# dental-uint-pedal_v1_0.net
KiCad netlist of a schematic drawn in Altium Designer
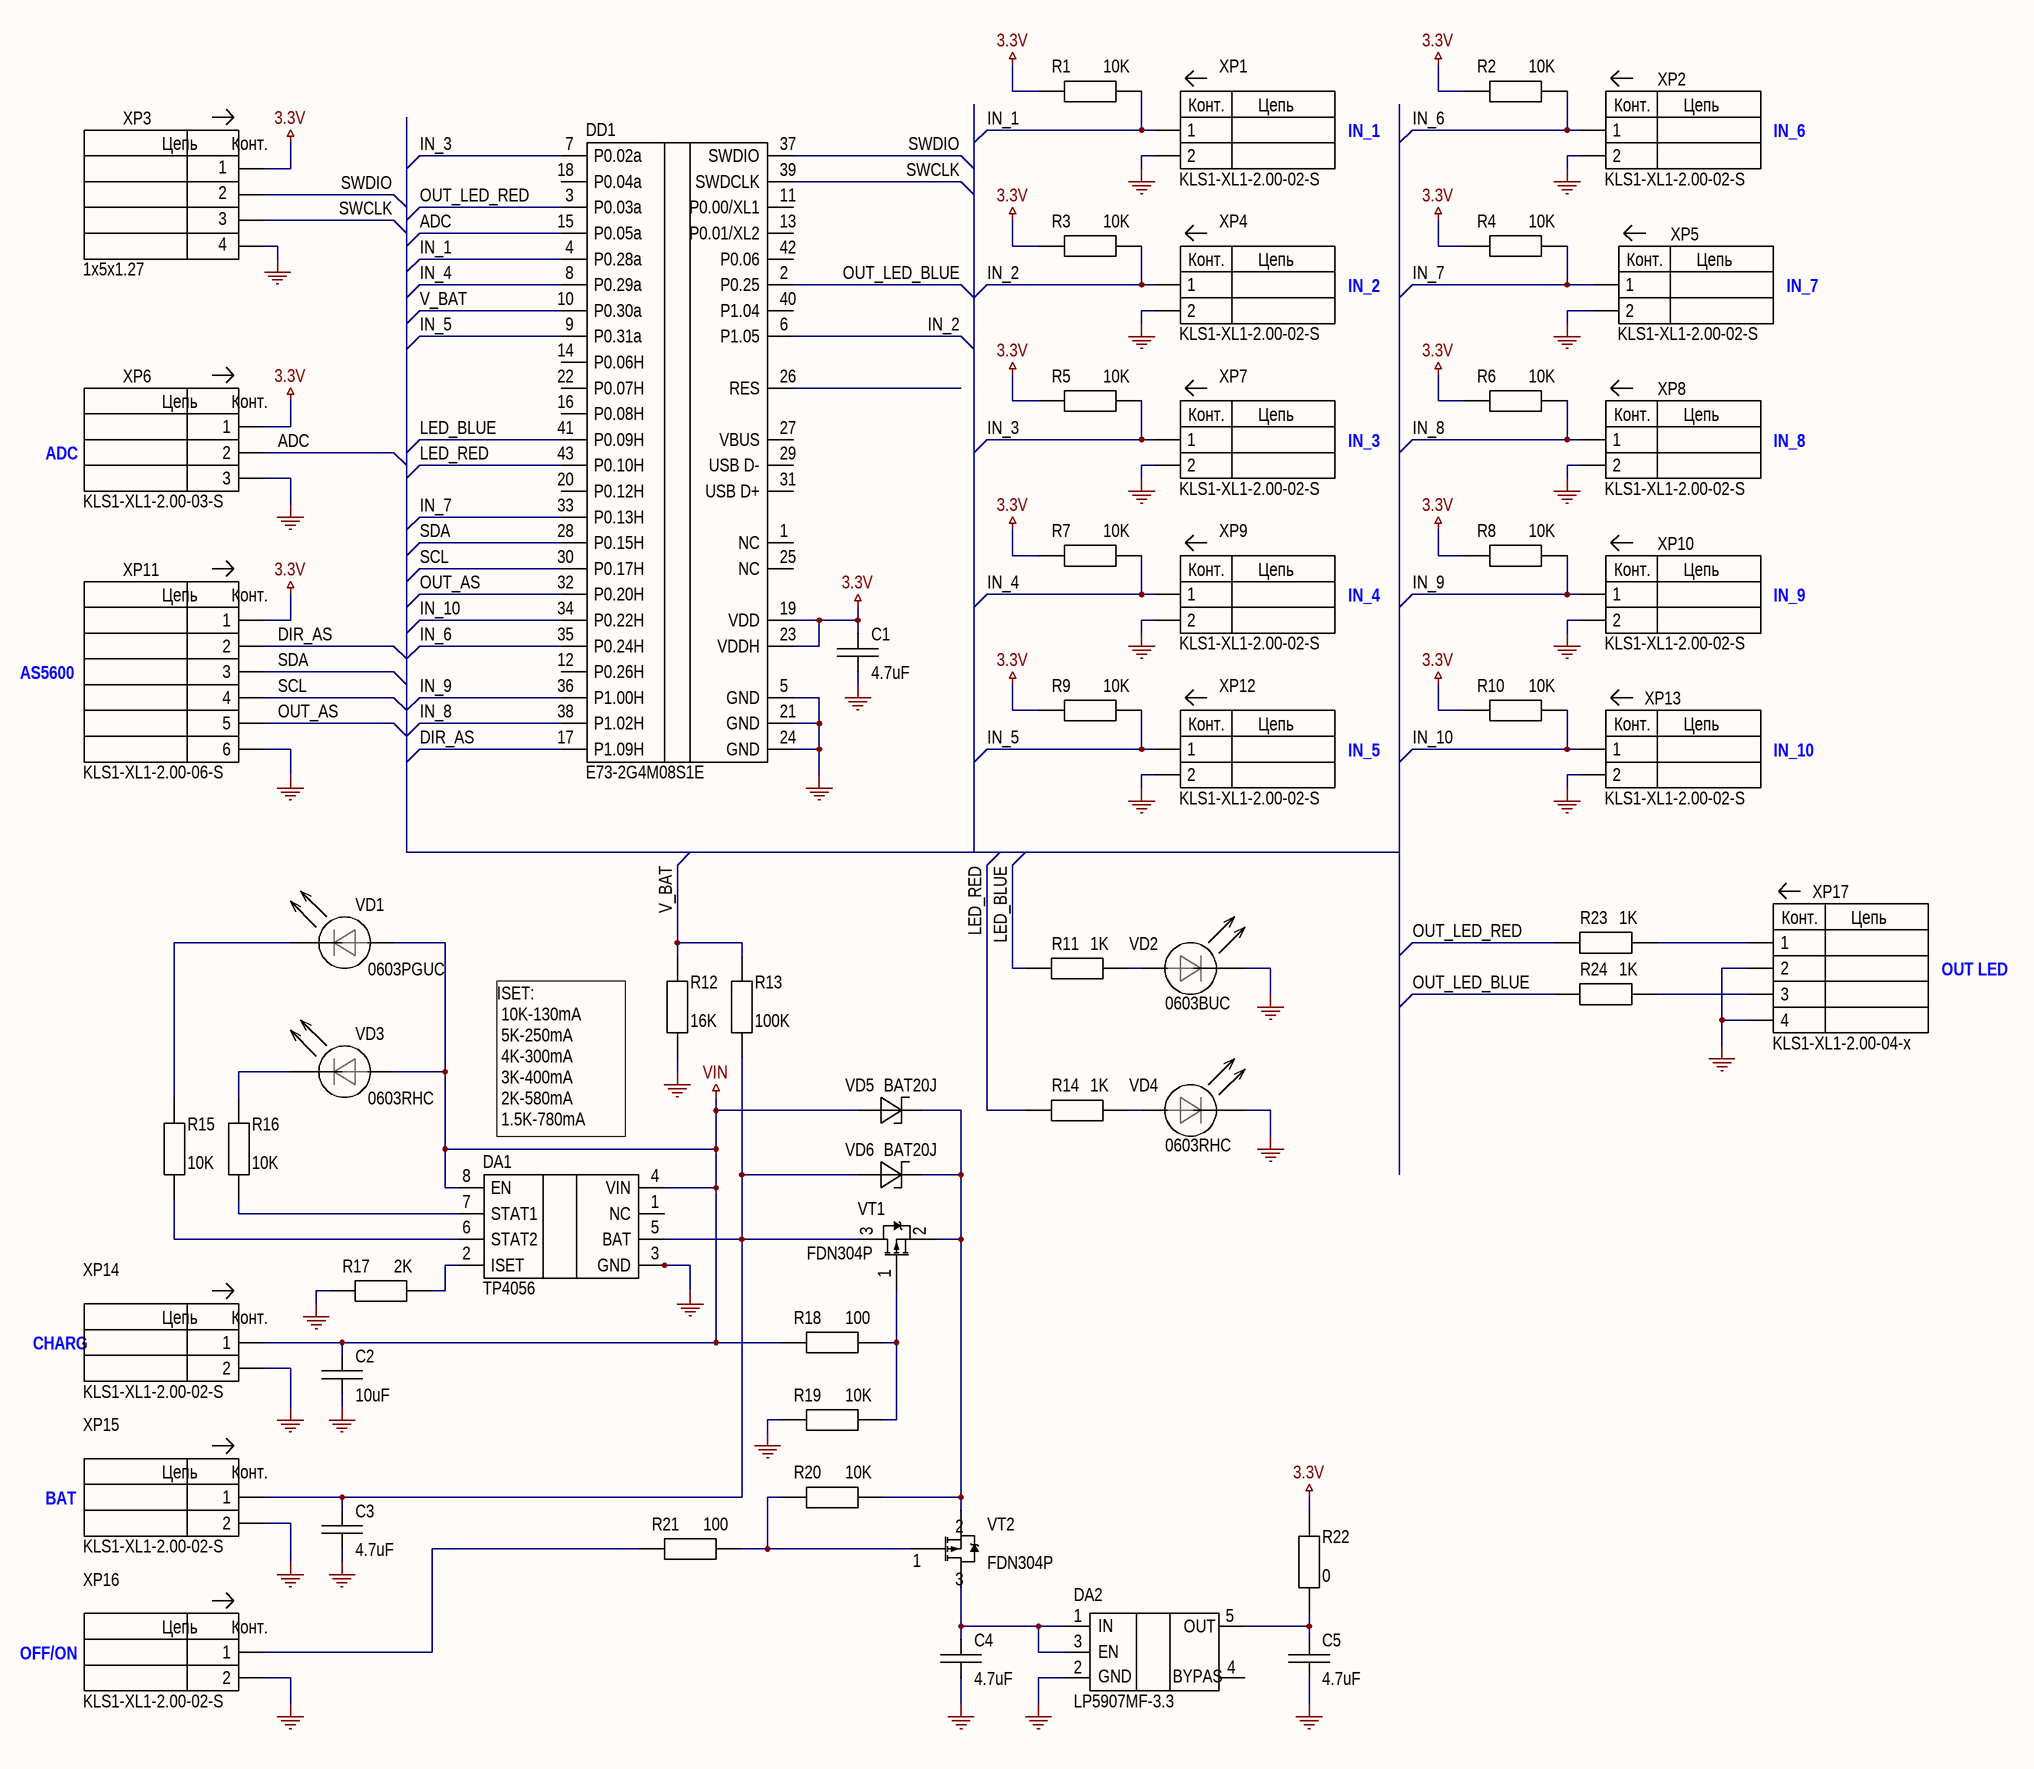
[diagram p0: dental-uint-pedal v1_0.SchDoc]

(export (version "E")
  (design (tool "Eeschema 10.0.6"))
  (components
    (comp (ref "C1")
      (value "4.7uF")
      (footprint "CC_0603")
      (description "Cap Ceramic, 0603, 4.7u, 10%, 25V, X5R (Sumsung)")
      (fields (field (name "Comment") "CL10A475KA8NQNC"))
      (libsource (lib "my_discrete_new") (part "C"))
    )
    (comp (ref "C2")
      (value "10uF")
      (footprint "CC_0603")
      (description "Cap Ceramic, 0603, 10u, 10%, 16V, X5R (Sumsung)")
      (fields (field (name "Comment") "CL10A106KP8NNNC"))
      (libsource (lib "my_discrete_new") (part "C"))
    )
    (comp (ref "C3")
      (value "4.7uF")
      (footprint "CC_0603")
      (description "Cap Ceramic, 0603, 4.7u, 10%, 25V, X5R (Sumsung)")
      (fields (field (name "Comment") "CL10A475KA8NQNC"))
      (libsource (lib "my_discrete_new") (part "C"))
    )
    (comp (ref "C4")
      (value "4.7uF")
      (footprint "CC_0603")
      (description "Cap Ceramic, 0603, 4.7u, 10%, 25V, X5R (Sumsung)")
      (fields (field (name "Comment") "CL10A475KA8NQNC"))
      (libsource (lib "my_discrete_new") (part "C"))
    )
    (comp (ref "C5")
      (value "4.7uF")
      (footprint "CC_0603")
      (description "Cap Ceramic, 0603, 4.7u, 10%, 25V, X5R (Sumsung)")
      (fields (field (name "Comment") "CL10A475KA8NQNC"))
      (libsource (lib "my_discrete_new") (part "C"))
    )
    (comp (ref "DA1")
      (value "TP4056")
      (footprint "SOIC-8N")
      (description "Battery Management")
      (libsource (lib "my_microschems_new") (part "TP4056"))
    )
    (comp (ref "DA2")
      (value "LP5907MF-3.3")
      (footprint "SOT-23-5")
      (description "LDO, SOT-23-5, 3.3v, 0.25А, @TI")
      (libsource (lib "my_microschems_new") (part "LP5907MF-3.3"))
    )
    (comp (ref "DD1")
      (value "E73-2G4M08S1E")
      (footprint "E73-2G4M08S1C")
      (description "nRF52833")
      (libsource (lib "my_microschems_new") (part "E73-2G4M08S1E"))
    )
    (comp (ref "R1")
      (value "10K")
      (footprint "RC_0603")
      (description "Res, 0603, 10K, 1%, 0.25W (ф. Yageo)")
      (fields (field (name "POWER") "0.25W") (field (name "Comment") "AC0603FR-0710KL"))
      (libsource (lib "my_discrete_new") (part "R"))
    )
    (comp (ref "R2")
      (value "10K")
      (footprint "RC_0603")
      (description "Res, 0603, 10K, 1%, 0.25W (ф. Yageo)")
      (fields (field (name "POWER") "0.25W") (field (name "Comment") "AC0603FR-0710KL"))
      (libsource (lib "my_discrete_new") (part "R"))
    )
    (comp (ref "R3")
      (value "10K")
      (footprint "RC_0603")
      (description "Res, 0603, 10K, 1%, 0.25W (ф. Yageo)")
      (fields (field (name "POWER") "0.25W") (field (name "Comment") "AC0603FR-0710KL"))
      (libsource (lib "my_discrete_new") (part "R"))
    )
    (comp (ref "R4")
      (value "10K")
      (footprint "RC_0603")
      (description "Res, 0603, 10K, 1%, 0.25W (ф. Yageo)")
      (fields (field (name "POWER") "0.25W") (field (name "Comment") "AC0603FR-0710KL"))
      (libsource (lib "my_discrete_new") (part "R"))
    )
    (comp (ref "R5")
      (value "10K")
      (footprint "RC_0603")
      (description "Res, 0603, 10K, 1%, 0.25W (ф. Yageo)")
      (fields (field (name "POWER") "0.25W") (field (name "Comment") "AC0603FR-0710KL"))
      (libsource (lib "my_discrete_new") (part "R"))
    )
    (comp (ref "R6")
      (value "10K")
      (footprint "RC_0603")
      (description "Res, 0603, 10K, 1%, 0.25W (ф. Yageo)")
      (fields (field (name "POWER") "0.25W") (field (name "Comment") "AC0603FR-0710KL"))
      (libsource (lib "my_discrete_new") (part "R"))
    )
    (comp (ref "R7")
      (value "10K")
      (footprint "RC_0603")
      (description "Res, 0603, 10K, 1%, 0.25W (ф. Yageo)")
      (fields (field (name "POWER") "0.25W") (field (name "Comment") "AC0603FR-0710KL"))
      (libsource (lib "my_discrete_new") (part "R"))
    )
    (comp (ref "R8")
      (value "10K")
      (footprint "RC_0603")
      (description "Res, 0603, 10K, 1%, 0.25W (ф. Yageo)")
      (fields (field (name "POWER") "0.25W") (field (name "Comment") "AC0603FR-0710KL"))
      (libsource (lib "my_discrete_new") (part "R"))
    )
    (comp (ref "R9")
      (value "10K")
      (footprint "RC_0603")
      (description "Res, 0603, 10K, 1%, 0.25W (ф. Yageo)")
      (fields (field (name "POWER") "0.25W") (field (name "Comment") "AC0603FR-0710KL"))
      (libsource (lib "my_discrete_new") (part "R"))
    )
    (comp (ref "R10")
      (value "10K")
      (footprint "RC_0603")
      (description "Res, 0603, 10K, 1%, 0.25W (ф. Yageo)")
      (fields (field (name "POWER") "0.25W") (field (name "Comment") "AC0603FR-0710KL"))
      (libsource (lib "my_discrete_new") (part "R"))
    )
    (comp (ref "R11")
      (value "1K")
      (footprint "RC_0603")
      (description "Res, 0603, 1K 1%, 0.25W (ф. Yageo)")
      (fields (field (name "POWER") "0.25W") (field (name "Comment") "AC0603FR-071KL"))
      (libsource (lib "my_discrete_new") (part "R"))
    )
    (comp (ref "R12")
      (value "16K")
      (footprint "RC_0603")
      (description "Res, 0603, 16K, 1%, 0.25W (ф. Yageo)")
      (fields (field (name "POWER") "0.25W") (field (name "Comment") "AC0603JR-0716KL"))
      (libsource (lib "my_discrete_new") (part "R"))
    )
    (comp (ref "R13")
      (value "100K")
      (footprint "RC_0603")
      (description "Res, 0603, 100K, 1%, 0.25W (ф. Yageo)")
      (fields (field (name "POWER") "0.25W") (field (name "Comment") "AC0603FR-07100KL"))
      (libsource (lib "my_discrete_new") (part "R"))
    )
    (comp (ref "R14")
      (value "1K")
      (footprint "RC_0603")
      (description "Res, 0603, 1K 1%, 0.25W (ф. Yageo)")
      (fields (field (name "POWER") "0.25W") (field (name "Comment") "AC0603FR-071KL"))
      (libsource (lib "my_discrete_new") (part "R"))
    )
    (comp (ref "R15")
      (value "10K")
      (footprint "RC_0603")
      (description "Res, 0603, 10K, 1%, 0.25W (ф. Yageo)")
      (fields (field (name "POWER") "0.25W") (field (name "Comment") "AC0603FR-0710KL"))
      (libsource (lib "my_discrete_new") (part "R"))
    )
    (comp (ref "R16")
      (value "10K")
      (footprint "RC_0603")
      (description "Res, 0603, 10K, 1%, 0.25W (ф. Yageo)")
      (fields (field (name "POWER") "0.25W") (field (name "Comment") "AC0603FR-0710KL"))
      (libsource (lib "my_discrete_new") (part "R"))
    )
    (comp (ref "R17")
      (value "2K")
      (footprint "RC_0603")
      (description "Res, 0603, 2K, 1%, 0.25W (ф. Yageo)")
      (fields (field (name "POWER") "0.25W") (field (name "Comment") "AC0603FR-072KL"))
      (libsource (lib "my_discrete_new") (part "R"))
    )
    (comp (ref "R18")
      (value "100")
      (footprint "RC_0603")
      (description "Res, 0603, 100, 1%, 0.25W (ф. Yageo)")
      (fields (field (name "POWER") "0.25W") (field (name "Comment") "RC0603FR-07100RL"))
      (libsource (lib "my_discrete_new") (part "R"))
    )
    (comp (ref "R19")
      (value "10K")
      (footprint "RC_0603")
      (description "Res, 0603, 10K, 1%, 0.25W (ф. Yageo)")
      (fields (field (name "POWER") "0.25W") (field (name "Comment") "AC0603FR-0710KL"))
      (libsource (lib "my_discrete_new") (part "R"))
    )
    (comp (ref "R20")
      (value "10K")
      (footprint "RC_0603")
      (description "Res, 0603, 10K, 1%, 0.25W (ф. Yageo)")
      (fields (field (name "POWER") "0.25W") (field (name "Comment") "AC0603FR-0710KL"))
      (libsource (lib "my_discrete_new") (part "R"))
    )
    (comp (ref "R21")
      (value "100")
      (footprint "RC_0603")
      (description "Res, 0603, 100, 1%, 0.25W (ф. Yageo)")
      (fields (field (name "POWER") "0.25W") (field (name "Comment") "RC0603FR-07100RL"))
      (libsource (lib "my_discrete_new") (part "R"))
    )
    (comp (ref "R22")
      (value "0")
      (footprint "RC_0603")
      (description "Res, 0603, 0, 1%, 0.25W (ф. Yageo)")
      (fields (field (name "POWER") "0.25W") (field (name "Comment") "AC0603FR-070RL"))
      (libsource (lib "my_discrete_new") (part "R"))
    )
    (comp (ref "R23")
      (value "1K")
      (footprint "RC_0603")
      (description "Res, 0603, 1K 1%, 0.25W (ф. Yageo)")
      (fields (field (name "POWER") "0.25W") (field (name "Comment") "AC0603FR-071KL"))
      (libsource (lib "my_discrete_new") (part "R"))
    )
    (comp (ref "R24")
      (value "1K")
      (footprint "RC_0603")
      (description "Res, 0603, 1K 1%, 0.25W (ф. Yageo)")
      (fields (field (name "POWER") "0.25W") (field (name "Comment") "AC0603FR-071KL"))
      (libsource (lib "my_discrete_new") (part "R"))
    )
    (comp (ref "VD1")
      (value "0603PGUC")
      (footprint "LED_0603")
      (description "Led, 0603, GREEN, 20mA, 125, 140MCD, CPMELEC")
      (libsource (lib "my_discrete_new") (part "LED"))
    )
    (comp (ref "VD2")
      (value "0603BUC")
      (footprint "LED_0603")
      (description "Led, 0603, BLUE, 20mA, 125, 140MCD, CPMELEC")
      (libsource (lib "my_discrete_new") (part "LED"))
    )
    (comp (ref "VD3")
      (value "0603RHC")
      (footprint "LED_0603")
      (description "Led, 0603, RED, 20mA, 125, 140MCD, CPMELEC")
      (libsource (lib "my_discrete_new") (part "LED"))
    )
    (comp (ref "VD4")
      (value "0603RHC")
      (footprint "LED_0603")
      (description "Led, 0603, RED, 20mA, 125, 140MCD, CPMELEC")
      (libsource (lib "my_discrete_new") (part "LED"))
    )
    (comp (ref "VD5")
      (value "BAT20J")
      (footprint "SOD-323")
      (libsource (lib "my_discrete_new") (part "D_schottky"))
    )
    (comp (ref "VD6")
      (value "BAT20J")
      (footprint "SOD-323")
      (libsource (lib "my_discrete_new") (part "D_schottky"))
    )
    (comp (ref "VT1")
      (value "FDN304P")
      (footprint "SOT-23-3")
      (description "HEXFET Power MOSFET")
      (libsource (lib "my_microschems_new") (part "IRLML6402"))
    )
    (comp (ref "VT2")
      (value "FDN304P")
      (footprint "SOT-23-3")
      (description "HEXFET Power MOSFET")
      (libsource (lib "my_microschems_new") (part "IRLML6402"))
    )
    (comp (ref "XP1")
      (value "KLS1-XL1-2.00-02-S")
      (footprint "KLS1-XL1-2.00-02-S")
      (description "2.0mm, 2pin, KLS")
      (fields (field (name "NAME") "IN_1"))
      (libsource (lib "my_connectors_new") (part "KLS1-XL1-2.00-02-x"))
    )
    (comp (ref "XP2")
      (value "KLS1-XL1-2.00-02-S")
      (footprint "KLS1-XL1-2.00-02-S")
      (description "2.0mm, 2pin, KLS")
      (fields (field (name "NAME") "IN_6"))
      (libsource (lib "my_connectors_new") (part "KLS1-XL1-2.00-02-x"))
    )
    (comp (ref "XP3")
      (value "1x5x1.27")
      (footprint "XT_1x4x1,27")
      (libsource (lib "my_connectors_new") (part "XT_1x4x1_27"))
    )
    (comp (ref "XP4")
      (value "KLS1-XL1-2.00-02-S")
      (footprint "KLS1-XL1-2.00-02-S")
      (description "2.0mm, 2pin, KLS")
      (fields (field (name "NAME") "IN_2"))
      (libsource (lib "my_connectors_new") (part "KLS1-XL1-2.00-02-x"))
    )
    (comp (ref "XP5")
      (value "KLS1-XL1-2.00-02-S")
      (footprint "KLS1-XL1-2.00-02-S")
      (description "2.0mm, 2pin, KLS")
      (fields (field (name "NAME") "IN_7"))
      (libsource (lib "my_connectors_new") (part "KLS1-XL1-2.00-02-x"))
    )
    (comp (ref "XP6")
      (value "KLS1-XL1-2.00-03-S")
      (footprint "KLS1-XL1-2.00-03-S")
      (description "2.0mm, 3pin, KLS")
      (fields (field (name "NAME") "ADC"))
      (libsource (lib "my_connectors_new") (part "KLS1-XL1-2.00-03-x"))
    )
    (comp (ref "XP7")
      (value "KLS1-XL1-2.00-02-S")
      (footprint "KLS1-XL1-2.00-02-S")
      (description "2.0mm, 2pin, KLS")
      (fields (field (name "NAME") "IN_3"))
      (libsource (lib "my_connectors_new") (part "KLS1-XL1-2.00-02-x"))
    )
    (comp (ref "XP8")
      (value "KLS1-XL1-2.00-02-S")
      (footprint "KLS1-XL1-2.00-02-S")
      (description "2.0mm, 2pin, KLS")
      (fields (field (name "NAME") "IN_8"))
      (libsource (lib "my_connectors_new") (part "KLS1-XL1-2.00-02-x"))
    )
    (comp (ref "XP9")
      (value "KLS1-XL1-2.00-02-S")
      (footprint "KLS1-XL1-2.00-02-S")
      (description "2.0mm, 2pin, KLS")
      (fields (field (name "NAME") "IN_4"))
      (libsource (lib "my_connectors_new") (part "KLS1-XL1-2.00-02-x"))
    )
    (comp (ref "XP10")
      (value "KLS1-XL1-2.00-02-S")
      (footprint "KLS1-XL1-2.00-02-S")
      (description "2.0mm, 2pin, KLS")
      (fields (field (name "NAME") "IN_9"))
      (libsource (lib "my_connectors_new") (part "KLS1-XL1-2.00-02-x"))
    )
    (comp (ref "XP11")
      (value "KLS1-XL1-2.00-06-S")
      (footprint "KLS1-XL1-2.00-06-S")
      (description "2.0mm, 6pin, KLS")
      (fields (field (name "NAME") "AS5600"))
      (libsource (lib "my_connectors_new") (part "KLS1-XL1-2.00-06-x"))
    )
    (comp (ref "XP12")
      (value "KLS1-XL1-2.00-02-S")
      (footprint "KLS1-XL1-2.00-02-S")
      (description "2.0mm, 2pin, KLS")
      (fields (field (name "NAME") "IN_5"))
      (libsource (lib "my_connectors_new") (part "KLS1-XL1-2.00-02-x"))
    )
    (comp (ref "XP13")
      (value "KLS1-XL1-2.00-02-S")
      (footprint "KLS1-XL1-2.00-02-S")
      (description "2.0mm, 2pin, KLS")
      (fields (field (name "NAME") "IN_10"))
      (libsource (lib "my_connectors_new") (part "KLS1-XL1-2.00-02-x"))
    )
    (comp (ref "XP14")
      (value "KLS1-XL1-2.00-02-S")
      (footprint "KLS1-XL1-2.00-02-S")
      (description "2.0mm, 2pin, KLS")
      (fields (field (name "NAME") "CHARG"))
      (libsource (lib "my_connectors_new") (part "KLS1-XL1-2.00-02-x"))
    )
    (comp (ref "XP15")
      (value "KLS1-XL1-2.00-02-S")
      (footprint "KLS1-XL1-2.00-02-S")
      (description "2.0mm, 2pin, KLS")
      (fields (field (name "NAME") "BAT"))
      (libsource (lib "my_connectors_new") (part "KLS1-XL1-2.00-02-x"))
    )
    (comp (ref "XP16")
      (value "KLS1-XL1-2.00-02-S")
      (footprint "KLS1-XL1-2.00-02-S")
      (description "2.0mm, 2pin, KLS")
      (fields (field (name "NAME") "OFF/ON"))
      (libsource (lib "my_connectors_new") (part "KLS1-XL1-2.00-02-x"))
    )
    (comp (ref "XP17")
      (value "KLS1-XL1-2.00-04-x")
      (footprint "KLS1-XL1-2.00-04-S")
      (description "2.0mm, 4pin, KLS")
      (fields (field (name "NAME") "OUT LED"))
      (libsource (lib "my_connectors_new") (part "KLS1-XL1-2.00-04-x"))
    )
  )
  (nets
    (net (code "1") (name "/ADC") (class "Default")
      (node (ref "DD1") (pin "15") (pinfunction "P0.05a_15") (pintype "passive"))
      (node (ref "XP6") (pin "2") (pinfunction "2_2") (pintype "passive"))
    )
    (net (code "2") (name "/DIR_AS") (class "Default")
      (node (ref "DD1") (pin "17") (pinfunction "P1.09H_17") (pintype "passive"))
      (node (ref "XP11") (pin "2") (pinfunction "2_2") (pintype "passive"))
    )
    (net (code "3") (name "/IN_1") (class "Default")
      (node (ref "DD1") (pin "4") (pinfunction "P0.28a_4") (pintype "passive"))
      (node (ref "R1") (pin "1") (pinfunction "1_1") (pintype "passive"))
      (node (ref "XP1") (pin "1") (pinfunction "1_1") (pintype "passive"))
    )
    (net (code "4") (name "/IN_2") (class "Default")
      (node (ref "DD1") (pin "6") (pinfunction "P1.05_6") (pintype "passive"))
      (node (ref "R3") (pin "1") (pinfunction "1_1") (pintype "passive"))
      (node (ref "XP4") (pin "1") (pinfunction "1_1") (pintype "passive"))
    )
    (net (code "5") (name "/IN_3") (class "Default")
      (node (ref "DD1") (pin "7") (pinfunction "P0.02a_7") (pintype "passive"))
      (node (ref "R5") (pin "1") (pinfunction "1_1") (pintype "passive"))
      (node (ref "XP7") (pin "1") (pinfunction "1_1") (pintype "passive"))
    )
    (net (code "6") (name "/IN_4") (class "Default")
      (node (ref "DD1") (pin "8") (pinfunction "P0.29a_8") (pintype "passive"))
      (node (ref "R7") (pin "1") (pinfunction "1_1") (pintype "passive"))
      (node (ref "XP9") (pin "1") (pinfunction "1_1") (pintype "passive"))
    )
    (net (code "7") (name "/IN_5") (class "Default")
      (node (ref "DD1") (pin "9") (pinfunction "P0.31a_9") (pintype "passive"))
      (node (ref "R9") (pin "1") (pinfunction "1_1") (pintype "passive"))
      (node (ref "XP12") (pin "1") (pinfunction "1_1") (pintype "passive"))
    )
    (net (code "8") (name "/IN_6") (class "Default")
      (node (ref "DD1") (pin "35") (pinfunction "P0.24H_35") (pintype "passive"))
      (node (ref "R2") (pin "1") (pinfunction "1_1") (pintype "passive"))
      (node (ref "XP2") (pin "1") (pinfunction "1_1") (pintype "passive"))
    )
    (net (code "9") (name "/IN_7") (class "Default")
      (node (ref "DD1") (pin "33") (pinfunction "P0.13H_33") (pintype "passive"))
      (node (ref "R4") (pin "1") (pinfunction "1_1") (pintype "passive"))
      (node (ref "XP5") (pin "1") (pinfunction "1_1") (pintype "passive"))
    )
    (net (code "10") (name "/IN_8") (class "Default")
      (node (ref "DD1") (pin "38") (pinfunction "P1.02H_38") (pintype "passive"))
      (node (ref "R6") (pin "1") (pinfunction "1_1") (pintype "passive"))
      (node (ref "XP8") (pin "1") (pinfunction "1_1") (pintype "passive"))
    )
    (net (code "11") (name "/IN_9") (class "Default")
      (node (ref "DD1") (pin "36") (pinfunction "P1.00H_36") (pintype "passive"))
      (node (ref "R8") (pin "1") (pinfunction "1_1") (pintype "passive"))
      (node (ref "XP10") (pin "1") (pinfunction "1_1") (pintype "passive"))
    )
    (net (code "12") (name "/IN_10") (class "Default")
      (node (ref "DD1") (pin "34") (pinfunction "P0.22H_34") (pintype "passive"))
      (node (ref "R10") (pin "1") (pinfunction "1_1") (pintype "passive"))
      (node (ref "XP13") (pin "1") (pinfunction "1_1") (pintype "passive"))
    )
    (net (code "13") (name "/LED_BLUE") (class "Default")
      (node (ref "DD1") (pin "41") (pinfunction "P0.09H_41") (pintype "passive"))
      (node (ref "R11") (pin "1") (pinfunction "1_1") (pintype "passive"))
    )
    (net (code "14") (name "/LED_RED") (class "Default")
      (node (ref "DD1") (pin "43") (pinfunction "P0.10H_43") (pintype "passive"))
      (node (ref "R14") (pin "1") (pinfunction "1_1") (pintype "passive"))
    )
    (net (code "15") (name "/OUT_AS") (class "Default")
      (node (ref "DD1") (pin "32") (pinfunction "P0.20H_32") (pintype "passive"))
      (node (ref "XP11") (pin "5") (pinfunction "5_5") (pintype "passive"))
    )
    (net (code "16") (name "/OUT_LED_BLUE") (class "Default")
      (node (ref "DD1") (pin "2") (pinfunction "P0.25_2") (pintype "passive"))
      (node (ref "R24") (pin "1") (pinfunction "1_1") (pintype "passive"))
    )
    (net (code "17") (name "/OUT_LED_RED") (class "Default")
      (node (ref "DD1") (pin "3") (pinfunction "P0.03a_3") (pintype "passive"))
      (node (ref "R23") (pin "1") (pinfunction "1_1") (pintype "passive"))
    )
    (net (code "18") (name "/SCL") (class "Default")
      (node (ref "DD1") (pin "30") (pinfunction "P0.17H_30") (pintype "passive"))
      (node (ref "XP11") (pin "4") (pinfunction "4_4") (pintype "passive"))
    )
    (net (code "19") (name "/SDA") (class "Default")
      (node (ref "DD1") (pin "28") (pinfunction "P0.15H_28") (pintype "passive"))
      (node (ref "XP11") (pin "3") (pinfunction "3_3") (pintype "passive"))
    )
    (net (code "20") (name "/SWCLK") (class "Default")
      (node (ref "DD1") (pin "39") (pinfunction "SWDCLK_39") (pintype "passive"))
      (node (ref "XP3") (pin "3") (pinfunction "3_3") (pintype "passive"))
    )
    (net (code "21") (name "/SWDIO") (class "Default")
      (node (ref "DD1") (pin "37") (pinfunction "SWDIO_37") (pintype "passive"))
      (node (ref "XP3") (pin "2") (pinfunction "2_2") (pintype "passive"))
    )
    (net (code "22") (name "/V_BAT") (class "Default")
      (node (ref "DD1") (pin "10") (pinfunction "P0.30a_10") (pintype "passive"))
      (node (ref "R12") (pin "2") (pinfunction "2_2") (pintype "passive"))
      (node (ref "R13") (pin "2") (pinfunction "2_2") (pintype "passive"))
    )
    (net (code "23") (name "3.3V") (class "Default")
      (node (ref "C1") (pin "2") (pinfunction "2_2") (pintype "passive"))
      (node (ref "DD1") (pin "19") (pinfunction "VDD_19") (pintype "passive"))
      (node (ref "DD1") (pin "23") (pinfunction "VDDH_23") (pintype "passive"))
      (node (ref "R1") (pin "2") (pinfunction "2_2") (pintype "passive"))
      (node (ref "R10") (pin "2") (pinfunction "2_2") (pintype "passive"))
      (node (ref "R2") (pin "2") (pinfunction "2_2") (pintype "passive"))
      (node (ref "R22") (pin "1") (pinfunction "1_1") (pintype "passive"))
      (node (ref "R3") (pin "2") (pinfunction "2_2") (pintype "passive"))
      (node (ref "R4") (pin "2") (pinfunction "2_2") (pintype "passive"))
      (node (ref "R5") (pin "2") (pinfunction "2_2") (pintype "passive"))
      (node (ref "R6") (pin "2") (pinfunction "2_2") (pintype "passive"))
      (node (ref "R7") (pin "2") (pinfunction "2_2") (pintype "passive"))
      (node (ref "R8") (pin "2") (pinfunction "2_2") (pintype "passive"))
      (node (ref "R9") (pin "2") (pinfunction "2_2") (pintype "passive"))
      (node (ref "XP11") (pin "1") (pinfunction "1_1") (pintype "passive"))
      (node (ref "XP3") (pin "1") (pinfunction "1_1") (pintype "passive"))
      (node (ref "XP6") (pin "1") (pinfunction "1_1") (pintype "passive"))
    )
    (net (code "24") (name "GND") (class "Default")
      (node (ref "C1") (pin "1") (pinfunction "1_1") (pintype "passive"))
      (node (ref "C2") (pin "1") (pinfunction "1_1") (pintype "passive"))
      (node (ref "C3") (pin "1") (pinfunction "1_1") (pintype "passive"))
      (node (ref "C4") (pin "1") (pinfunction "1_1") (pintype "passive"))
      (node (ref "C5") (pin "1") (pinfunction "1_1") (pintype "passive"))
      (node (ref "DA1") (pin "3") (pinfunction "GND_3") (pintype "power_in"))
      (node (ref "DA1") (pin "9") (pinfunction "PAD_9") (pintype "power_in"))
      (node (ref "DA2") (pin "2") (pinfunction "GND_2") (pintype "passive"))
      (node (ref "DD1") (pin "21") (pinfunction "GND_21") (pintype "passive"))
      (node (ref "DD1") (pin "24") (pinfunction "GND_24") (pintype "passive"))
      (node (ref "DD1") (pin "5") (pinfunction "GND_5") (pintype "passive"))
      (node (ref "R12") (pin "1") (pinfunction "1_1") (pintype "passive"))
      (node (ref "R17") (pin "2") (pinfunction "2_2") (pintype "passive"))
      (node (ref "R19") (pin "1") (pinfunction "1_1") (pintype "passive"))
      (node (ref "VD2") (pin "2") (pinfunction "C_2") (pintype "passive"))
      (node (ref "VD4") (pin "2") (pinfunction "C_2") (pintype "passive"))
      (node (ref "XP1") (pin "2") (pinfunction "2_2") (pintype "passive"))
      (node (ref "XP10") (pin "2") (pinfunction "2_2") (pintype "passive"))
      (node (ref "XP11") (pin "6") (pinfunction "6_6") (pintype "passive"))
      (node (ref "XP12") (pin "2") (pinfunction "2_2") (pintype "passive"))
      (node (ref "XP13") (pin "2") (pinfunction "2_2") (pintype "passive"))
      (node (ref "XP14") (pin "2") (pinfunction "2_2") (pintype "passive"))
      (node (ref "XP15") (pin "2") (pinfunction "2_2") (pintype "passive"))
      (node (ref "XP16") (pin "2") (pinfunction "2_2") (pintype "passive"))
      (node (ref "XP17") (pin "2") (pinfunction "2_2") (pintype "passive"))
      (node (ref "XP17") (pin "4") (pinfunction "4_4") (pintype "passive"))
      (node (ref "XP2") (pin "2") (pinfunction "2_2") (pintype "passive"))
      (node (ref "XP3") (pin "4") (pinfunction "4_4") (pintype "passive"))
      (node (ref "XP4") (pin "2") (pinfunction "2_2") (pintype "passive"))
      (node (ref "XP5") (pin "2") (pinfunction "2_2") (pintype "passive"))
      (node (ref "XP6") (pin "3") (pinfunction "3_3") (pintype "passive"))
      (node (ref "XP7") (pin "2") (pinfunction "2_2") (pintype "passive"))
      (node (ref "XP8") (pin "2") (pinfunction "2_2") (pintype "passive"))
      (node (ref "XP9") (pin "2") (pinfunction "2_2") (pintype "passive"))
    )
    (net (code "25") (name "Net-(DA1-BAT)") (class "Default")
      (node (ref "C3") (pin "2") (pinfunction "2_2") (pintype "passive"))
      (node (ref "DA1") (pin "5") (pinfunction "BAT_5") (pintype "power_in"))
      (node (ref "R13") (pin "1") (pinfunction "1_1") (pintype "passive"))
      (node (ref "VD6") (pin "1") (pinfunction "A_1") (pintype "passive"))
      (node (ref "VT1") (pin "3") (pinfunction "D_3") (pintype "passive"))
      (node (ref "XP15") (pin "1") (pinfunction "1_1") (pintype "passive"))
    )
    (net (code "26") (name "Net-(DA1-ISET)") (class "Default")
      (node (ref "DA1") (pin "2") (pinfunction "ISET_2") (pintype "power_in"))
      (node (ref "R17") (pin "1") (pinfunction "1_1") (pintype "passive"))
    )
    (net (code "27") (name "Net-(DA1-STAT1)") (class "Default")
      (node (ref "DA1") (pin "7") (pinfunction "STAT1_7") (pintype "power_in"))
      (node (ref "R16") (pin "1") (pinfunction "1_1") (pintype "passive"))
    )
    (net (code "28") (name "Net-(DA1-STAT2)") (class "Default")
      (node (ref "DA1") (pin "6") (pinfunction "STAT2_6") (pintype "power_in"))
      (node (ref "R15") (pin "1") (pinfunction "1_1") (pintype "passive"))
    )
    (net (code "29") (name "Net-(DA2-EN)") (class "Default")
      (node (ref "C4") (pin "2") (pinfunction "2_2") (pintype "passive"))
      (node (ref "DA2") (pin "1") (pinfunction "IN_1") (pintype "passive"))
      (node (ref "DA2") (pin "3") (pinfunction "EN_3") (pintype "passive"))
      (node (ref "VT2") (pin "3") (pinfunction "D_3") (pintype "passive"))
    )
    (net (code "30") (name "Net-(DA2-OUT)") (class "Default")
      (node (ref "C5") (pin "2") (pinfunction "2_2") (pintype "passive"))
      (node (ref "DA2") (pin "5") (pinfunction "OUT_5") (pintype "passive"))
      (node (ref "R22") (pin "2") (pinfunction "2_2") (pintype "passive"))
    )
    (net (code "31") (name "Net-(R21-Pad2)") (class "Default")
      (node (ref "R21") (pin "2") (pinfunction "2_2") (pintype "passive"))
      (node (ref "XP16") (pin "1") (pinfunction "1_1") (pintype "passive"))
    )
    (net (code "32") (name "Net-(R23-Pad2)") (class "Default")
      (node (ref "R23") (pin "2") (pinfunction "2_2") (pintype "passive"))
      (node (ref "XP17") (pin "1") (pinfunction "1_1") (pintype "passive"))
    )
    (net (code "33") (name "Net-(R24-Pad2)") (class "Default")
      (node (ref "R24") (pin "2") (pinfunction "2_2") (pintype "passive"))
      (node (ref "XP17") (pin "3") (pinfunction "3_3") (pintype "passive"))
    )
    (net (code "34") (name "Net-(VD1-C)") (class "Default")
      (node (ref "R15") (pin "2") (pinfunction "2_2") (pintype "passive"))
      (node (ref "VD1") (pin "2") (pinfunction "C_2") (pintype "passive"))
    )
    (net (code "35") (name "Net-(VD2-A)") (class "Default")
      (node (ref "R11") (pin "2") (pinfunction "2_2") (pintype "passive"))
      (node (ref "VD2") (pin "1") (pinfunction "A_1") (pintype "passive"))
    )
    (net (code "36") (name "Net-(VD3-C)") (class "Default")
      (node (ref "R16") (pin "2") (pinfunction "2_2") (pintype "passive"))
      (node (ref "VD3") (pin "2") (pinfunction "C_2") (pintype "passive"))
    )
    (net (code "37") (name "Net-(VD4-A)") (class "Default")
      (node (ref "R14") (pin "2") (pinfunction "2_2") (pintype "passive"))
      (node (ref "VD4") (pin "1") (pinfunction "A_1") (pintype "passive"))
    )
    (net (code "38") (name "Net-(VD5-C)") (class "Default")
      (node (ref "R20") (pin "2") (pinfunction "2_2") (pintype "passive"))
      (node (ref "VD5") (pin "2") (pinfunction "C_2") (pintype "passive"))
      (node (ref "VD6") (pin "2") (pinfunction "C_2") (pintype "passive"))
      (node (ref "VT1") (pin "2") (pinfunction "S_2") (pintype "passive"))
      (node (ref "VT2") (pin "2") (pinfunction "S_2") (pintype "passive"))
    )
    (net (code "39") (name "Net-(VT1-G)") (class "Default")
      (node (ref "R18") (pin "1") (pinfunction "1_1") (pintype "passive"))
      (node (ref "R19") (pin "2") (pinfunction "2_2") (pintype "passive"))
      (node (ref "VT1") (pin "1") (pinfunction "G_1") (pintype "passive"))
    )
    (net (code "40") (name "Net-(VT2-G)") (class "Default")
      (node (ref "R20") (pin "1") (pinfunction "1_1") (pintype "passive"))
      (node (ref "R21") (pin "1") (pinfunction "1_1") (pintype "passive"))
      (node (ref "VT2") (pin "1") (pinfunction "G_1") (pintype "passive"))
    )
    (net (code "41") (name "VIN") (class "Default")
      (node (ref "C2") (pin "2") (pinfunction "2_2") (pintype "passive"))
      (node (ref "DA1") (pin "4") (pinfunction "VIN_4") (pintype "power_in"))
      (node (ref "DA1") (pin "8") (pinfunction "EN_8") (pintype "power_in"))
      (node (ref "R18") (pin "2") (pinfunction "2_2") (pintype "passive"))
      (node (ref "VD1") (pin "1") (pinfunction "A_1") (pintype "passive"))
      (node (ref "VD3") (pin "1") (pinfunction "A_1") (pintype "passive"))
      (node (ref "VD5") (pin "1") (pinfunction "A_1") (pintype "passive"))
      (node (ref "XP14") (pin "1") (pinfunction "1_1") (pintype "passive"))
    )
    (net (code "42") (name "unconnected-(DA1-NC-Pad1)") (class "Default")
      (node (ref "DA1") (pin "1") (pinfunction "NC_1") (pintype "power_in"))
    )
    (net (code "43") (name "unconnected-(DA2-NC-Pad4)") (class "Default")
      (node (ref "DA2") (pin "4") (pinfunction "NC_4") (pintype "passive"))
    )
    (net (code "44") (name "unconnected-(DD1-NC-Pad1)") (class "Default")
      (node (ref "DD1") (pin "1") (pinfunction "NC_1") (pintype "passive"))
    )
    (net (code "45") (name "unconnected-(DD1-NC-Pad25)") (class "Default")
      (node (ref "DD1") (pin "25") (pinfunction "NC_25") (pintype "passive"))
    )
    (net (code "46") (name "unconnected-(DD1-P0.00{slash}XL1-Pad11)") (class "Default")
      (node (ref "DD1") (pin "11") (pinfunction "P0.00/XL1_11") (pintype "passive"))
    )
    (net (code "47") (name "unconnected-(DD1-P0.01{slash}XL2-Pad13)") (class "Default")
      (node (ref "DD1") (pin "13") (pinfunction "P0.01/XL2_13") (pintype "passive"))
    )
    (net (code "48") (name "unconnected-(DD1-P0.04a-Pad18)") (class "Default")
      (node (ref "DD1") (pin "18") (pinfunction "P0.04a_18") (pintype "passive"))
    )
    (net (code "49") (name "unconnected-(DD1-P0.06-Pad42)") (class "Default")
      (node (ref "DD1") (pin "42") (pinfunction "P0.06_42") (pintype "passive"))
    )
    (net (code "50") (name "unconnected-(DD1-P0.06H-Pad14)") (class "Default")
      (node (ref "DD1") (pin "14") (pinfunction "P0.06H_14") (pintype "passive"))
    )
    (net (code "51") (name "unconnected-(DD1-P0.07H-Pad22)") (class "Default")
      (node (ref "DD1") (pin "22") (pinfunction "P0.07H_22") (pintype "passive"))
    )
    (net (code "52") (name "unconnected-(DD1-P0.08H-Pad16)") (class "Default")
      (node (ref "DD1") (pin "16") (pinfunction "P0.08H_16") (pintype "passive"))
    )
    (net (code "53") (name "unconnected-(DD1-P0.12H-Pad20)") (class "Default")
      (node (ref "DD1") (pin "20") (pinfunction "P0.12H_20") (pintype "passive"))
    )
    (net (code "54") (name "unconnected-(DD1-P0.26H-Pad12)") (class "Default")
      (node (ref "DD1") (pin "12") (pinfunction "P0.26H_12") (pintype "passive"))
    )
    (net (code "55") (name "unconnected-(DD1-P1.04-Pad40)") (class "Default")
      (node (ref "DD1") (pin "40") (pinfunction "P1.04_40") (pintype "passive"))
    )
    (net (code "56") (name "unconnected-(DD1-RES-Pad26)") (class "Default")
      (node (ref "DD1") (pin "26") (pinfunction "RES_26") (pintype "passive"))
    )
    (net (code "57") (name "unconnected-(DD1-USB_D+-Pad31)") (class "Default")
      (node (ref "DD1") (pin "31") (pinfunction "USB_D+_31") (pintype "passive"))
    )
    (net (code "58") (name "unconnected-(DD1-USB_D--Pad29)") (class "Default")
      (node (ref "DD1") (pin "29") (pinfunction "USB_D-_29") (pintype "passive"))
    )
    (net (code "59") (name "unconnected-(DD1-VBUS-Pad27)") (class "Default")
      (node (ref "DD1") (pin "27") (pinfunction "VBUS_27") (pintype "passive"))
    )
  )
)
